# schematic_rs232_ttl_converter.net
KiCad netlist of a schematic drawn in EasyEDA
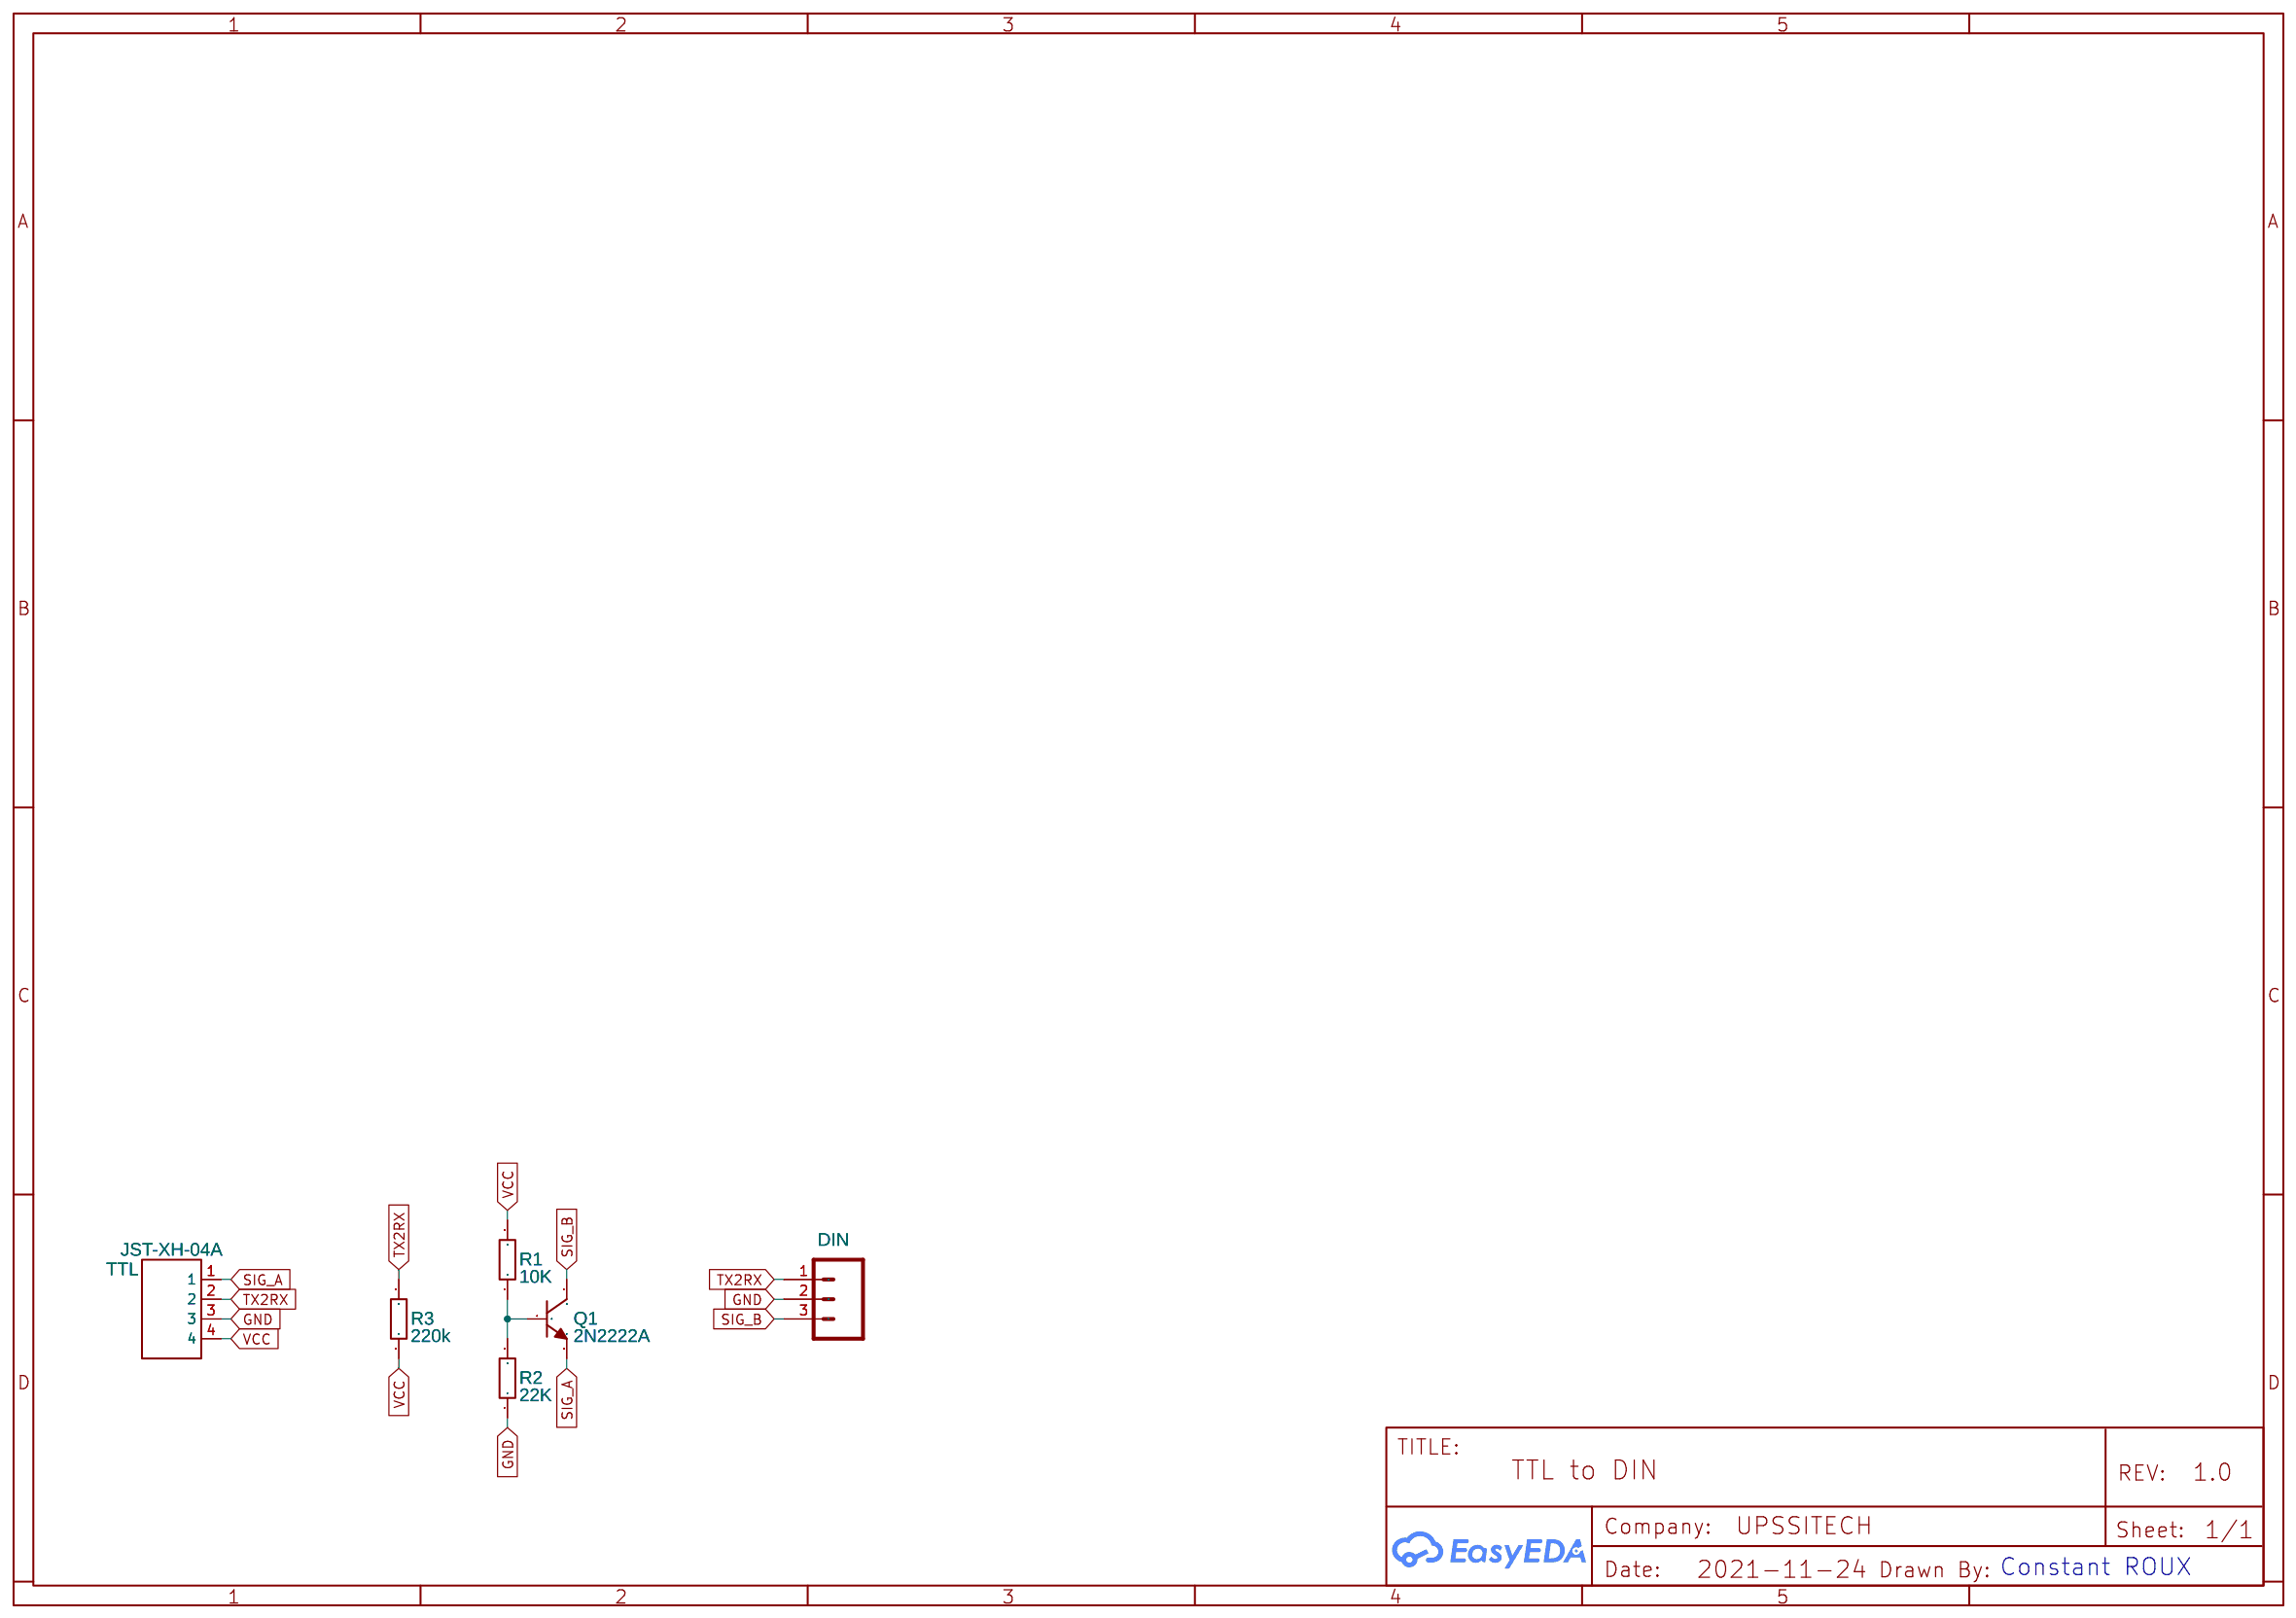
[diagram p0: schematic sheet]

(export (version "E")
  (design (tool "Eeschema 10.0.6"))
  (components
    (comp (ref "DIN")
      (value "JST-XH-1X03-2.50MM-THM")
      (fields (field (name "BOM_Supplier Part") "455-2248-ND"))
      (libsource (lib "") (part "JST-XH-1X03-2.50MM-THM"))
    )
    (comp (ref "Q1")
      (value "2N2222A")
      (fields (field (name "BOM_Supplier Part") "C358533"))
      (libsource (lib "") (part "2N2222A"))
    )
    (comp (ref "R1")
      (value "10K")
      (fields
        (field (name "BOM_Manufacturer Part") "CFR0W4J0102A50")
        (field (name "BOM_Supplier Part") "C61293")
      )
      (libsource (lib "") (part "CFR0W4J0102A50"))
    )
    (comp (ref "R2")
      (value "22K")
      (fields
        (field (name "BOM_Manufacturer Part") "CFR0W4J0102A50")
        (field (name "BOM_Supplier Part") "C61293")
      )
      (libsource (lib "") (part "CFR0W4J0102A50"))
    )
    (comp (ref "R3")
      (value "220k")
      (fields
        (field (name "BOM_Manufacturer Part") "CFR0W4J0102A50")
        (field (name "BOM_Supplier Part") "C61293")
      )
      (libsource (lib "") (part "CFR0W4J0102A50"))
    )
    (comp (ref "TTL") (value "JST-XH-04A") (libsource (lib "") (part "JST-XH-04A")))
  )
  (nets
    (net (code "1") (name "GND") (class "Default")
      (node (ref "DIN") (pin "2") (pinfunction "2_2") (pintype "unspecified"))
      (node (ref "R2") (pin "1") (pinfunction "1_1") (pintype "input"))
      (node (ref "TTL") (pin "3") (pinfunction "3_3") (pintype "unspecified"))
    )
    (net (code "2") (name "Net-(Q1-B)") (class "Default")
      (node (ref "Q1") (pin "2") (pinfunction "B_2") (pintype "unspecified"))
      (node (ref "R1") (pin "1") (pinfunction "1_1") (pintype "input"))
      (node (ref "R2") (pin "2") (pinfunction "2_2") (pintype "input"))
    )
    (net (code "3") (name "SIG_A") (class "Default")
      (node (ref "Q1") (pin "3") (pinfunction "E_3") (pintype "unspecified"))
      (node (ref "TTL") (pin "1") (pinfunction "1_1") (pintype "unspecified"))
    )
    (net (code "4") (name "SIG_B") (class "Default")
      (node (ref "DIN") (pin "3") (pinfunction "3_3") (pintype "unspecified"))
      (node (ref "Q1") (pin "1") (pinfunction "C_1") (pintype "unspecified"))
    )
    (net (code "5") (name "TX2RX") (class "Default")
      (node (ref "DIN") (pin "1") (pinfunction "1_1") (pintype "unspecified"))
      (node (ref "R3") (pin "2") (pinfunction "2_2") (pintype "input"))
      (node (ref "TTL") (pin "2") (pinfunction "2_2") (pintype "unspecified"))
    )
    (net (code "6") (name "VCC") (class "Default")
      (node (ref "R1") (pin "2") (pinfunction "2_2") (pintype "input"))
      (node (ref "R3") (pin "1") (pinfunction "1_1") (pintype "input"))
      (node (ref "TTL") (pin "4") (pinfunction "4_4") (pintype "unspecified"))
    )
  )
)
